# 2230506226.net
KiCad netlist of a schematic drawn in EasyEDA Pro
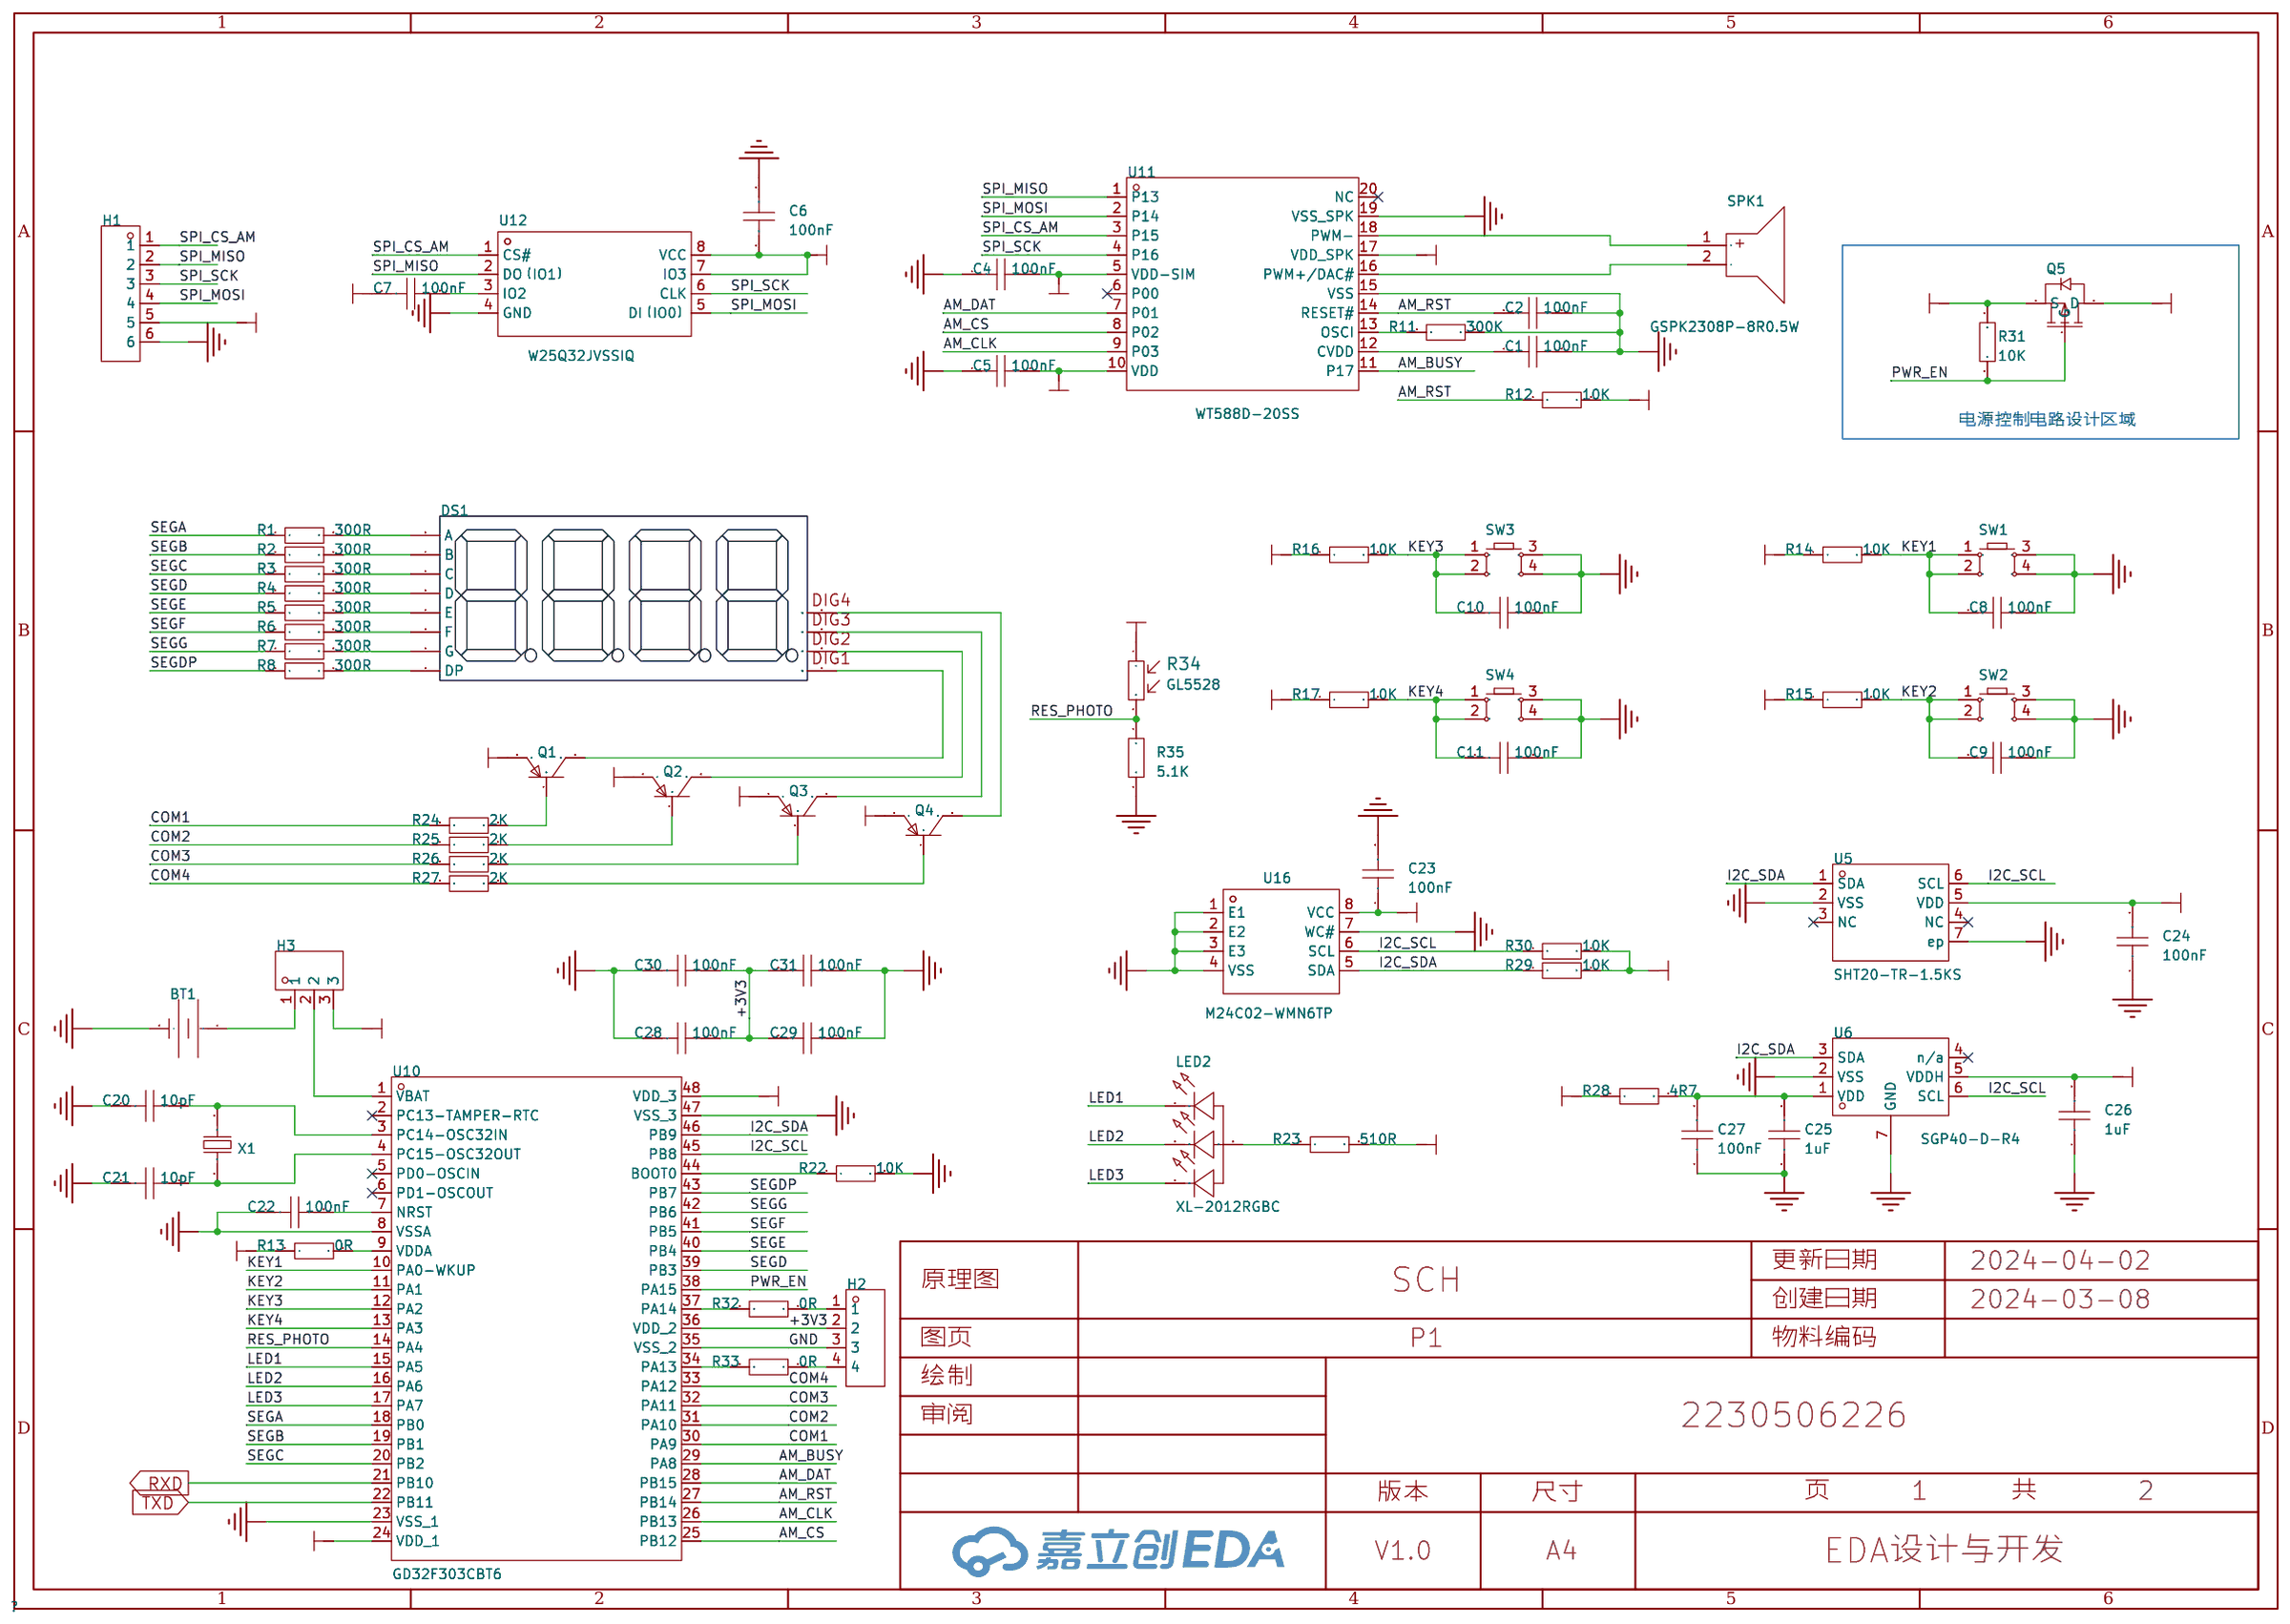
[diagram p0: P1]
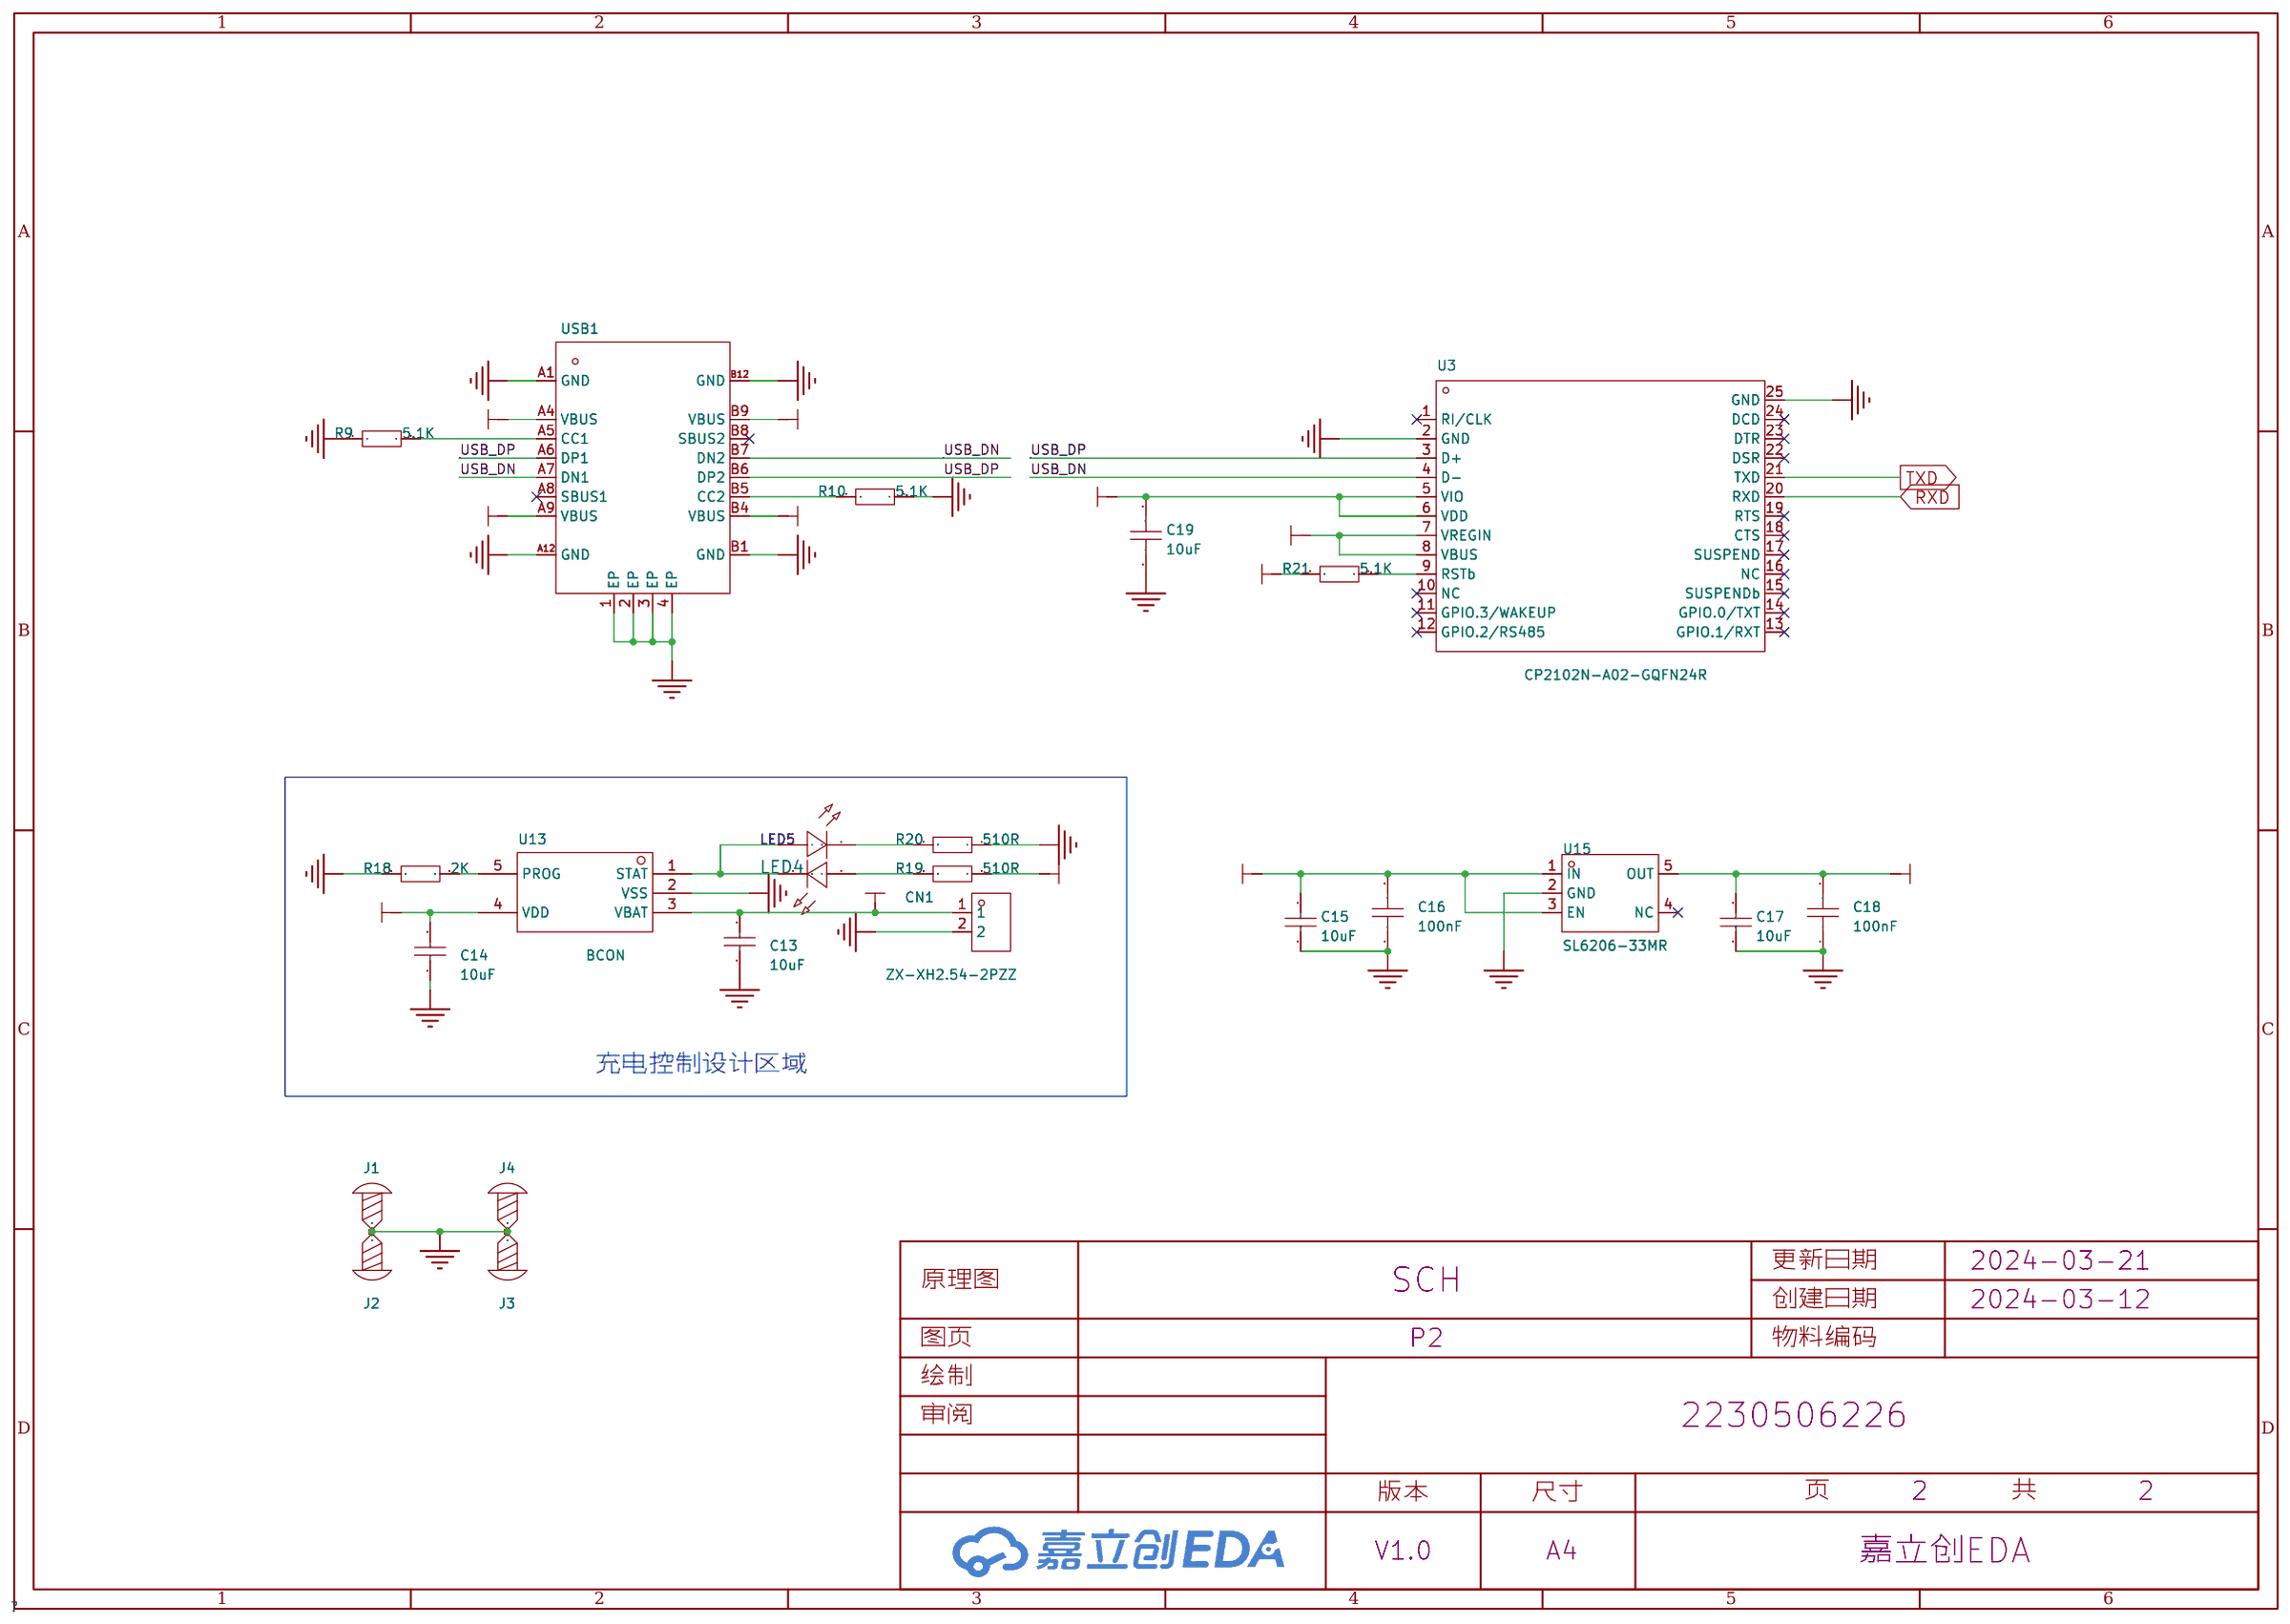
[diagram p1: P2]

(export (version "E")
  (design (tool "Eeschema 10.0.6"))
  (components
    (comp (ref "BT1")
      (value "BS-12-B3AA003")
      (footprint "easyedapro:BAT-SMD_BS-12-B3AA011")
      (description "连接器类型:电池底座;适用电池规格:CR1220;工作温度范围:-25°C~+85°C;")
      (fields (field (name "Manufacturer") "MYOUNG(美阳)"))
      (libsource (lib "easyedapro") (part "BS-12-B3AA003"))
    )
    (comp (ref "C1")
      (value "100nF")
      (footprint "easyedapro:C0805")
      (libsource (lib "easyedapro") (part "CapAcitance"))
    )
    (comp (ref "C2")
      (value "100nF")
      (footprint "easyedapro:C0805")
      (libsource (lib "easyedapro") (part "CapAcitance"))
    )
    (comp (ref "C4")
      (value "100nF")
      (footprint "easyedapro:C0805")
      (libsource (lib "easyedapro") (part "CapAcitance"))
    )
    (comp (ref "C5")
      (value "100nF")
      (footprint "easyedapro:C0805")
      (libsource (lib "easyedapro") (part "CapAcitance"))
    )
    (comp (ref "C6")
      (value "100nF")
      (footprint "easyedapro:C0805")
      (libsource (lib "easyedapro") (part "CapAcitance"))
    )
    (comp (ref "C7")
      (value "100nF")
      (footprint "easyedapro:C0805")
      (libsource (lib "easyedapro") (part "CapAcitance"))
    )
    (comp (ref "C8")
      (value "100nF")
      (footprint "easyedapro:C0805")
      (libsource (lib "easyedapro") (part "CapAcitance"))
    )
    (comp (ref "C9")
      (value "100nF")
      (footprint "easyedapro:C0805")
      (libsource (lib "easyedapro") (part "CapAcitance"))
    )
    (comp (ref "C10")
      (value "100nF")
      (footprint "easyedapro:C0805")
      (libsource (lib "easyedapro") (part "CapAcitance"))
    )
    (comp (ref "C11")
      (value "100nF")
      (footprint "easyedapro:C0805")
      (libsource (lib "easyedapro") (part "CapAcitance"))
    )
    (comp (ref "C20")
      (value "10pF")
      (footprint "easyedapro:C0805")
      (libsource (lib "easyedapro") (part "CapAcitance"))
    )
    (comp (ref "C21")
      (value "10pF")
      (footprint "easyedapro:C0805")
      (libsource (lib "easyedapro") (part "CapAcitance"))
    )
    (comp (ref "C22")
      (value "100nF")
      (footprint "easyedapro:C0805")
      (libsource (lib "easyedapro") (part "CapAcitance"))
    )
    (comp (ref "C23")
      (value "100nF")
      (footprint "easyedapro:C0805")
      (libsource (lib "easyedapro") (part "CapAcitance"))
    )
    (comp (ref "C24")
      (value "100nF")
      (footprint "easyedapro:C0805")
      (libsource (lib "easyedapro") (part "CapAcitance"))
    )
    (comp (ref "C25")
      (value "1uF")
      (footprint "easyedapro:C0805")
      (libsource (lib "easyedapro") (part "CapAcitance"))
    )
    (comp (ref "C26")
      (value "1uF")
      (footprint "easyedapro:C0805")
      (libsource (lib "easyedapro") (part "CapAcitance"))
    )
    (comp (ref "C27")
      (value "100nF")
      (footprint "easyedapro:C0805")
      (libsource (lib "easyedapro") (part "CapAcitance"))
    )
    (comp (ref "C28")
      (value "100nF")
      (footprint "easyedapro:C0805")
      (libsource (lib "easyedapro") (part "CapAcitance"))
    )
    (comp (ref "C29")
      (value "100nF")
      (footprint "easyedapro:C0805")
      (libsource (lib "easyedapro") (part "CapAcitance"))
    )
    (comp (ref "C30")
      (value "100nF")
      (footprint "easyedapro:C0805")
      (libsource (lib "easyedapro") (part "CapAcitance"))
    )
    (comp (ref "C31")
      (value "100nF")
      (footprint "easyedapro:C0805")
      (libsource (lib "easyedapro") (part "CapAcitance"))
    )
    (comp (ref "DS1")
      (value "~")
      (footprint "easyedapro:LED-SEG-TH_FJ5461AH")
      (libsource (lib "easyedapro") (part "LED_SEG_TH_0.56x4"))
    )
    (comp (ref "H1")
      (value "~")
      (footprint "easyedapro:HDR-TH_6P-P2.54-V-F")
      (libsource (lib "easyedapro") (part "Header-Female-2.54_1x6"))
    )
    (comp (ref "H2")
      (value "~")
      (footprint "easyedapro:HDR-TH_4P-P2.54-V-F")
      (libsource (lib "easyedapro") (part "2.54-1*4P母"))
    )
    (comp (ref "H3")
      (value "Jumper3")
      (footprint "easyedapro:HDR-TH_3P-P2.54-V-M-A")
      (libsource (lib "easyedapro") (part "JUMPER3"))
    )
    (comp (ref "LED2")
      (value "XL-2012RGBC")
      (footprint "easyedapro:LED-SMD_4P-L2.0-W1.3-BR")
      (fields (field (name "Manufacturer") "XINGLIGHT(成兴光)"))
      (libsource (lib "easyedapro") (part "XL-2012RGBC"))
    )
    (comp (ref "Q1")
      (value "~")
      (footprint "easyedapro:S8550P_SOT")
      (libsource (lib "easyedapro") (part "PNP"))
    )
    (comp (ref "Q2")
      (value "~")
      (footprint "easyedapro:S8550P_SOT")
      (libsource (lib "easyedapro") (part "PNP"))
    )
    (comp (ref "Q3")
      (value "~")
      (footprint "easyedapro:S8550P_SOT")
      (libsource (lib "easyedapro") (part "PNP"))
    )
    (comp (ref "Q4")
      (value "~")
      (footprint "easyedapro:S8550P_SOT")
      (libsource (lib "easyedapro") (part "PNP"))
    )
    (comp (ref "Q5")
      (value "~")
      (footprint "easyedapro:AO3401A_SOT-23-3")
      (libsource (lib "easyedapro") (part "P_MOS"))
    )
    (comp (ref "R1") (value "300R") (footprint "easyedapro:R0805") (libsource (lib "easyedapro") (part "电阻")))
    (comp (ref "R2") (value "300R") (footprint "easyedapro:R0805") (libsource (lib "easyedapro") (part "电阻")))
    (comp (ref "R3") (value "300R") (footprint "easyedapro:R0805") (libsource (lib "easyedapro") (part "电阻")))
    (comp (ref "R4") (value "300R") (footprint "easyedapro:R0805") (libsource (lib "easyedapro") (part "电阻")))
    (comp (ref "R5") (value "300R") (footprint "easyedapro:R0805") (libsource (lib "easyedapro") (part "电阻")))
    (comp (ref "R6") (value "300R") (footprint "easyedapro:R0805") (libsource (lib "easyedapro") (part "电阻")))
    (comp (ref "R7") (value "300R") (footprint "easyedapro:R0805") (libsource (lib "easyedapro") (part "电阻")))
    (comp (ref "R8") (value "300R") (footprint "easyedapro:R0805") (libsource (lib "easyedapro") (part "电阻")))
    (comp (ref "R11")
      (value "300K")
      (footprint "easyedapro:R0805")
      (libsource (lib "easyedapro") (part "电阻"))
    )
    (comp (ref "R12") (value "10K") (footprint "easyedapro:R0805") (libsource (lib "easyedapro") (part "电阻")))
    (comp (ref "R13") (value "0R") (footprint "easyedapro:R0805") (libsource (lib "easyedapro") (part "电阻")))
    (comp (ref "R14") (value "10K") (footprint "easyedapro:R0805") (libsource (lib "easyedapro") (part "电阻")))
    (comp (ref "R15") (value "10K") (footprint "easyedapro:R0805") (libsource (lib "easyedapro") (part "电阻")))
    (comp (ref "R16") (value "10K") (footprint "easyedapro:R0805") (libsource (lib "easyedapro") (part "电阻")))
    (comp (ref "R17") (value "10K") (footprint "easyedapro:R0805") (libsource (lib "easyedapro") (part "电阻")))
    (comp (ref "R22") (value "10K") (footprint "easyedapro:R0805") (libsource (lib "easyedapro") (part "电阻")))
    (comp (ref "R23")
      (value "510R")
      (footprint "easyedapro:R0805")
      (libsource (lib "easyedapro") (part "电阻"))
    )
    (comp (ref "R24") (value "2K") (footprint "easyedapro:R0805") (libsource (lib "easyedapro") (part "电阻")))
    (comp (ref "R25") (value "2K") (footprint "easyedapro:R0805") (libsource (lib "easyedapro") (part "电阻")))
    (comp (ref "R26") (value "2K") (footprint "easyedapro:R0805") (libsource (lib "easyedapro") (part "电阻")))
    (comp (ref "R27") (value "2K") (footprint "easyedapro:R0805") (libsource (lib "easyedapro") (part "电阻")))
    (comp (ref "R28") (value "4R7") (footprint "easyedapro:R0805") (libsource (lib "easyedapro") (part "电阻")))
    (comp (ref "R29") (value "10K") (footprint "easyedapro:R0805") (libsource (lib "easyedapro") (part "电阻")))
    (comp (ref "R30") (value "10K") (footprint "easyedapro:R0805") (libsource (lib "easyedapro") (part "电阻")))
    (comp (ref "R31") (value "10K") (footprint "easyedapro:R0805") (libsource (lib "easyedapro") (part "电阻")))
    (comp (ref "R32") (value "0R") (footprint "easyedapro:R0805") (libsource (lib "easyedapro") (part "电阻")))
    (comp (ref "R33") (value "0R") (footprint "easyedapro:R0805") (libsource (lib "easyedapro") (part "电阻")))
    (comp (ref "R34")
      (value "GL5528")
      (footprint "easyedapro:RES-TH_L5.1-W4.3-P3.40-D0.5")
      (description "暗电阻:1MΩ;亮电阻 @ 10Lux:8kΩ~20kΩ;光谱峰值(波长):540nm;")
      (fields (field (name "Manufacturer") "森霸"))
      (libsource (lib "easyedapro") (part "GL5528"))
    )
    (comp (ref "R35")
      (value "5.1K")
      (footprint "easyedapro:R0805")
      (libsource (lib "easyedapro") (part "电阻"))
    )
    (comp (ref "SPK1")
      (value "GSPK2308P-8R0.5W")
      (footprint "easyedapro:SPK-TH_BD23.0-P10.00-D0.8-L-RD")
      (fields (field (name "Manufacturer") "INGHAi(赢海)"))
      (libsource (lib "easyedapro") (part "GSPK2308P-8R0.5W"))
    )
    (comp (ref "SW1")
      (value "~")
      (footprint "easyedapro:Key_SMD_12x12x7.3")
      (libsource (lib "easyedapro") (part "轻触按键"))
    )
    (comp (ref "SW2")
      (value "~")
      (footprint "easyedapro:Key_SMD_12x12x7.3")
      (libsource (lib "easyedapro") (part "轻触按键"))
    )
    (comp (ref "SW3")
      (value "~")
      (footprint "easyedapro:Key_SMD_12x12x7.3")
      (libsource (lib "easyedapro") (part "轻触按键"))
    )
    (comp (ref "SW4")
      (value "~")
      (footprint "easyedapro:Key_SMD_12x12x7.3")
      (libsource (lib "easyedapro") (part "轻触按键"))
    )
    (comp (ref "U5")
      (value "SHT20-TR-1.5KS")
      (footprint "easyedapro:DFN-6_L3.0-W3.0-P0.95-TR-EP")
      (description "接口类型:I2C;")
      (fields (field (name "Manufacturer") "Sensirion(瑞士盛思锐)"))
      (libsource (lib "easyedapro") (part "SHT20"))
    )
    (comp (ref "U6")
      (value "SGP40-D-R4")
      (footprint "easyedapro:DFN-6_L2.4-W2.4-P0.80-TL-EP")
      (description "气体类型:空气质量;精度:-;")
      (fields (field (name "Manufacturer") "Sensirion(瑞士盛思锐)"))
      (libsource (lib "easyedapro") (part "SGP40-D-R4"))
    )
    (comp (ref "U10")
      (value "GD32F303CBT6")
      (footprint "easyedapro:LQFP-48_L7.0-W7.0-P0.50-LS9.0-BL")
      (description "CPU内核:CM4;程序存储容量:128KB;RAM总容量:32KB;GPIO端口数量:37;工作电压范围:-;CPU最大主频:120MHz;程序存储器类型:FLASH;")
      (fields (field (name "Manufacturer") "GigaDevice(兆易创新)"))
      (libsource (lib "easyedapro") (part "GD32F303CBT6"))
    )
    (comp (ref "U11")
      (value "WT588D-20SS")
      (footprint "easyedapro:SSOP-20_L7.2-W5.3-P0.65-LS7.8-BL")
      (description "高品质语音芯片")
      (fields (field (name "Manufacturer") "WT(唯创知音)"))
      (libsource (lib "easyedapro") (part "WT588D"))
    )
    (comp (ref "U12")
      (value "W25Q32JVSSIQ")
      (footprint "easyedapro:SOIC-8_L5.3-W5.3-P1.27-LS8.0-BL")
      (description "接口类型:SPI;存储容量:32Mbit;")
      (fields (field (name "Manufacturer") "WINBOND(华邦)"))
      (libsource (lib "easyedapro") (part "W25Q32JVSSIQ"))
    )
    (comp (ref "U16")
      (value "M24C02-WMN6TP")
      (footprint "easyedapro:SOIC-8_L4.9-W3.9-P1.27-LS6.0-BL")
      (description "接口类型:I2C;存储容量:2Kbit;")
      (fields (field (name "Manufacturer") "ST(意法半导体)"))
      (libsource (lib "easyedapro") (part "M24C02-WMN6TP"))
    )
    (comp (ref "X1")
      (value "32.768kHz")
      (footprint "easyedapro:FC-135R_L3.2-W1.5")
      (description "晶振类型:贴片晶振;频率:32.768kHz;常温频差:±20ppm;外接负载电容:12.5pF;")
      (fields (field (name "Manufacturer Part") "Q13FC13500004") (field (name "Manufacturer") "EPSON(爱普生)"))
      (libsource (lib "easyedapro") (part "Q13FC1350000400"))
    )
    (comp (ref "C13")
      (value "10uF")
      (footprint "easyedapro:C1206")
      (description "容值:10uF;精度:±10%;额定电压:50V;材质(温度系数):X5R;")
      (fields
        (field (name "Manufacturer Part") "CL31A106KBHNNNE")
        (field (name "Manufacturer") "SAMSUNG(三星)")
      )
      (libsource (lib "easyedapro") (part "CL31A106KBHNNNE"))
    )
    (comp (ref "C14")
      (value "10uF")
      (footprint "easyedapro:C1206")
      (description "容值:10uF;精度:±10%;额定电压:50V;材质(温度系数):X5R;")
      (fields
        (field (name "Manufacturer Part") "CL31A106KBHNNNE")
        (field (name "Manufacturer") "SAMSUNG(三星)")
      )
      (libsource (lib "easyedapro") (part "CL31A106KBHNNNE"))
    )
    (comp (ref "C15")
      (value "10uF")
      (footprint "easyedapro:C1206")
      (description "容值:10uF;精度:±10%;额定电压:50V;材质(温度系数):X5R;")
      (fields
        (field (name "Manufacturer Part") "CL31A106KBHNNNE")
        (field (name "Manufacturer") "SAMSUNG(三星)")
      )
      (libsource (lib "easyedapro") (part "CL31A106KBHNNNE"))
    )
    (comp (ref "C16")
      (value "100nF")
      (footprint "easyedapro:C0805")
      (libsource (lib "easyedapro") (part "CapAcitance"))
    )
    (comp (ref "C17")
      (value "10uF")
      (footprint "easyedapro:C1206")
      (description "容值:10uF;精度:±10%;额定电压:50V;材质(温度系数):X5R;")
      (fields
        (field (name "Manufacturer Part") "CL31A106KBHNNNE")
        (field (name "Manufacturer") "SAMSUNG(三星)")
      )
      (libsource (lib "easyedapro") (part "CL31A106KBHNNNE"))
    )
    (comp (ref "C18")
      (value "100nF")
      (footprint "easyedapro:C0805")
      (libsource (lib "easyedapro") (part "CapAcitance"))
    )
    (comp (ref "C19")
      (value "10uF")
      (footprint "easyedapro:C0805")
      (libsource (lib "easyedapro") (part "CapAcitance"))
    )
    (comp (ref "CN1")
      (value "ZX-XH2.54-2PZZ")
      (footprint "easyedapro:CONN-TH_2P-P2.50_HX25003-2A")
      (fields (field (name "Manufacturer") "Megastar(兆星)"))
      (libsource (lib "easyedapro") (part "ZX-XH2.54-2PZZ"))
    )
    (comp (ref "J1") (value "~") (footprint "easyedapro:M2螺丝") (libsource (lib "easyedapro") (part "螺丝孔")))
    (comp (ref "J2") (value "~") (footprint "easyedapro:M2螺丝") (libsource (lib "easyedapro") (part "螺丝孔")))
    (comp (ref "J3") (value "~") (footprint "easyedapro:M2螺丝") (libsource (lib "easyedapro") (part "螺丝孔")))
    (comp (ref "J4") (value "~") (footprint "easyedapro:M2螺丝") (libsource (lib "easyedapro") (part "螺丝孔")))
    (comp (ref "LED4")
      (value "~")
      (footprint "easyedapro:LED_0805")
      (libsource (lib "easyedapro") (part "LED_R"))
    )
    (comp (ref "LED5")
      (value "~")
      (footprint "easyedapro:LED_0805")
      (libsource (lib "easyedapro") (part "LED_G"))
    )
    (comp (ref "R9") (value "5.1K") (footprint "easyedapro:R0805") (libsource (lib "easyedapro") (part "电阻")))
    (comp (ref "R10")
      (value "5.1K")
      (footprint "easyedapro:R0805")
      (libsource (lib "easyedapro") (part "电阻"))
    )
    (comp (ref "R18") (value "2K") (footprint "easyedapro:R0805") (libsource (lib "easyedapro") (part "电阻")))
    (comp (ref "R19")
      (value "510R")
      (footprint "easyedapro:R0805")
      (libsource (lib "easyedapro") (part "电阻"))
    )
    (comp (ref "R20")
      (value "510R")
      (footprint "easyedapro:R0805")
      (libsource (lib "easyedapro") (part "电阻"))
    )
    (comp (ref "R21")
      (value "5.1K")
      (footprint "easyedapro:R0805")
      (libsource (lib "easyedapro") (part "电阻"))
    )
    (comp (ref "U3")
      (value "CP2102N-A02-GQFN24R")
      (footprint "easyedapro:QFN-24_L4.0-W4.0-P0.50-TL-EP2.6")
      (description "应用功能:USB转UART;接口协议:UART;")
      (fields (field (name "Manufacturer") "SKYWORKS/SILICON LABS(芯科)"))
      (libsource (lib "easyedapro") (part "CP2102N-A02-GQFN24R"))
    )
    (comp (ref "U13") (value "BCON") (libsource (lib "easyedapro") (part "BCON")))
    (comp (ref "U15")
      (value "SL6206-33MR")
      (footprint "easyedapro:SOT-23-5_L2.9-W1.6-P0.95-LS2.8-BL")
      (description "输出类型:-;")
      (fields (field (name "Manufacturer") "Slkor(萨科微)"))
      (libsource (lib "easyedapro") (part "SL6206-33MR"))
    )
    (comp (ref "USB1")
      (value "~")
      (footprint "easyedapro:USB_TYPE-C-16P")
      (libsource (lib "easyedapro") (part "USB_TYPE-C-16P"))
    )
  )
  (nets
    (net (code "1") (name "+3V3") (class "Default")
      (node (ref "C17") (pin "2") (pinfunction "2_2") (pintype "input"))
      (node (ref "C18") (pin "2") (pinfunction "2_2") (pintype "input"))
      (node (ref "C19") (pin "2") (pinfunction "2_2") (pintype "input"))
      (node (ref "C23") (pin "1") (pinfunction "1_1") (pintype "input"))
      (node (ref "C28") (pin "1") (pinfunction "1_1") (pintype "input"))
      (node (ref "C29") (pin "2") (pinfunction "2_2") (pintype "input"))
      (node (ref "C30") (pin "1") (pinfunction "1_1") (pintype "input"))
      (node (ref "C31") (pin "2") (pinfunction "2_2") (pintype "input"))
      (node (ref "C4") (pin "2") (pinfunction "2_2") (pintype "input"))
      (node (ref "C5") (pin "2") (pinfunction "2_2") (pintype "input"))
      (node (ref "C6") (pin "2") (pinfunction "2_2") (pintype "input"))
      (node (ref "C7") (pin "1") (pinfunction "1_1") (pintype "input"))
      (node (ref "H1") (pin "5") (pinfunction "5_5") (pintype "unspecified"))
      (node (ref "H2") (pin "2") (pinfunction "2_2") (pintype "unspecified"))
      (node (ref "H3") (pin "3") (pinfunction "3_3") (pintype "input"))
      (node (ref "Q1") (pin "2") (pinfunction "E_2") (pintype "input"))
      (node (ref "Q2") (pin "2") (pinfunction "E_2") (pintype "input"))
      (node (ref "Q3") (pin "2") (pinfunction "E_2") (pintype "input"))
      (node (ref "Q4") (pin "2") (pinfunction "E_2") (pintype "input"))
      (node (ref "Q5") (pin "2") (pinfunction "S_2") (pintype "input"))
      (node (ref "R12") (pin "2") (pinfunction "2_2") (pintype "input"))
      (node (ref "R13") (pin "1") (pinfunction "1_1") (pintype "input"))
      (node (ref "R14") (pin "1") (pinfunction "1_1") (pintype "input"))
      (node (ref "R15") (pin "1") (pinfunction "1_1") (pintype "input"))
      (node (ref "R16") (pin "1") (pinfunction "1_1") (pintype "input"))
      (node (ref "R17") (pin "1") (pinfunction "1_1") (pintype "input"))
      (node (ref "R21") (pin "2") (pinfunction "2_2") (pintype "input"))
      (node (ref "R23") (pin "2") (pinfunction "2_2") (pintype "input"))
      (node (ref "R29") (pin "2") (pinfunction "2_2") (pintype "input"))
      (node (ref "R30") (pin "2") (pinfunction "2_2") (pintype "input"))
      (node (ref "R31") (pin "1") (pinfunction "1_1") (pintype "input"))
      (node (ref "R34") (pin "1") (pinfunction "1_1") (pintype "input"))
      (node (ref "U10") (pin "24") (pinfunction "VDD_1_24") (pintype "unspecified"))
      (node (ref "U10") (pin "36") (pinfunction "VDD_2_36") (pintype "unspecified"))
      (node (ref "U10") (pin "48") (pinfunction "VDD_3_48") (pintype "unspecified"))
      (node (ref "U11") (pin "10") (pinfunction "VDD_10") (pintype "input"))
      (node (ref "U11") (pin "17") (pinfunction "VDD_SPK_17") (pintype "input"))
      (node (ref "U11") (pin "5") (pinfunction "VDD-SIM_5") (pintype "input"))
      (node (ref "U12") (pin "7") (pinfunction "IO3_7") (pintype "unspecified"))
      (node (ref "U12") (pin "8") (pinfunction "VCC_8") (pintype "unspecified"))
      (node (ref "U15") (pin "5") (pinfunction "OUT_5") (pintype "unspecified"))
      (node (ref "U16") (pin "8") (pinfunction "VCC_8") (pintype "unspecified"))
      (node (ref "U3") (pin "5") (pinfunction "VIO_5") (pintype "unspecified"))
      (node (ref "U3") (pin "6") (pinfunction "VDD_6") (pintype "unspecified"))
    )
    (net (code "2") (name "+VS") (class "Default")
      (node (ref "C24") (pin "2") (pinfunction "2_2") (pintype "input"))
      (node (ref "C26") (pin "2") (pinfunction "2_2") (pintype "input"))
      (node (ref "Q5") (pin "3") (pinfunction "D_3") (pintype "input"))
      (node (ref "R28") (pin "1") (pinfunction "1_1") (pintype "input"))
      (node (ref "U5") (pin "5") (pinfunction "VDD_5") (pintype "unspecified"))
      (node (ref "U6") (pin "5") (pinfunction "VDDH_5") (pintype "unspecified"))
    )
    (net (code "3") (name "AM_BUSY") (class "Default")
      (node (ref "U10") (pin "29") (pinfunction "PA8_29") (pintype "unspecified"))
      (node (ref "U11") (pin "11") (pinfunction "P17_11") (pintype "input"))
    )
    (net (code "4") (name "AM_CLK") (class "Default")
      (node (ref "U10") (pin "26") (pinfunction "PB13_26") (pintype "unspecified"))
      (node (ref "U11") (pin "9") (pinfunction "P03_9") (pintype "input"))
    )
    (net (code "5") (name "AM_CS") (class "Default")
      (node (ref "U10") (pin "25") (pinfunction "PB12_25") (pintype "unspecified"))
      (node (ref "U11") (pin "8") (pinfunction "P02_8") (pintype "input"))
    )
    (net (code "6") (name "AM_DAT") (class "Default")
      (node (ref "U10") (pin "28") (pinfunction "PB15_28") (pintype "unspecified"))
      (node (ref "U11") (pin "7") (pinfunction "P01_7") (pintype "input"))
    )
    (net (code "7") (name "AM_RST") (class "Default")
      (node (ref "C2") (pin "1") (pinfunction "1_1") (pintype "input"))
      (node (ref "R12") (pin "1") (pinfunction "1_1") (pintype "input"))
      (node (ref "U10") (pin "27") (pinfunction "PB14_27") (pintype "unspecified"))
      (node (ref "U11") (pin "14") (pinfunction "RESET#_14") (pintype "input"))
    )
    (net (code "8") (name "COM1") (class "Default")
      (node (ref "R24") (pin "1") (pinfunction "1_1") (pintype "input"))
      (node (ref "U10") (pin "30") (pinfunction "PA9_30") (pintype "unspecified"))
    )
    (net (code "9") (name "COM2") (class "Default")
      (node (ref "R25") (pin "1") (pinfunction "1_1") (pintype "input"))
      (node (ref "U10") (pin "31") (pinfunction "PA10_31") (pintype "unspecified"))
    )
    (net (code "10") (name "COM3") (class "Default")
      (node (ref "R26") (pin "1") (pinfunction "1_1") (pintype "input"))
      (node (ref "U10") (pin "32") (pinfunction "PA11_32") (pintype "unspecified"))
    )
    (net (code "11") (name "COM4") (class "Default")
      (node (ref "R27") (pin "1") (pinfunction "1_1") (pintype "input"))
      (node (ref "U10") (pin "33") (pinfunction "PA12_33") (pintype "unspecified"))
    )
    (net (code "12") (name "GND") (class "Default")
      (node (ref "BT1") (pin "2") (pinfunction "-_2") (pintype "unspecified"))
      (node (ref "C1") (pin "2") (pinfunction "2_2") (pintype "input"))
      (node (ref "C10") (pin "2") (pinfunction "2_2") (pintype "input"))
      (node (ref "C11") (pin "2") (pinfunction "2_2") (pintype "input"))
      (node (ref "C13") (pin "2") (pinfunction "2_2") (pintype "input"))
      (node (ref "C14") (pin "2") (pinfunction "2_2") (pintype "input"))
      (node (ref "C15") (pin "1") (pinfunction "1_1") (pintype "input"))
      (node (ref "C16") (pin "1") (pinfunction "1_1") (pintype "input"))
      (node (ref "C17") (pin "1") (pinfunction "1_1") (pintype "input"))
      (node (ref "C18") (pin "1") (pinfunction "1_1") (pintype "input"))
      (node (ref "C19") (pin "1") (pinfunction "1_1") (pintype "input"))
      (node (ref "C2") (pin "2") (pinfunction "2_2") (pintype "input"))
      (node (ref "C20") (pin "1") (pinfunction "1_1") (pintype "input"))
      (node (ref "C21") (pin "1") (pinfunction "1_1") (pintype "input"))
      (node (ref "C22") (pin "1") (pinfunction "1_1") (pintype "input"))
      (node (ref "C23") (pin "2") (pinfunction "2_2") (pintype "input"))
      (node (ref "C24") (pin "1") (pinfunction "1_1") (pintype "input"))
      (node (ref "C25") (pin "1") (pinfunction "1_1") (pintype "input"))
      (node (ref "C26") (pin "1") (pinfunction "1_1") (pintype "input"))
      (node (ref "C27") (pin "1") (pinfunction "1_1") (pintype "input"))
      (node (ref "C28") (pin "2") (pinfunction "2_2") (pintype "input"))
      (node (ref "C29") (pin "1") (pinfunction "1_1") (pintype "input"))
      (node (ref "C30") (pin "2") (pinfunction "2_2") (pintype "input"))
      (node (ref "C31") (pin "1") (pinfunction "1_1") (pintype "input"))
      (node (ref "C4") (pin "1") (pinfunction "1_1") (pintype "input"))
      (node (ref "C5") (pin "1") (pinfunction "1_1") (pintype "input"))
      (node (ref "C6") (pin "1") (pinfunction "1_1") (pintype "input"))
      (node (ref "C8") (pin "2") (pinfunction "2_2") (pintype "input"))
      (node (ref "C9") (pin "2") (pinfunction "2_2") (pintype "input"))
      (node (ref "CN1") (pin "2") (pinfunction "2_2") (pintype "unspecified"))
      (node (ref "H1") (pin "6") (pinfunction "6_6") (pintype "unspecified"))
      (node (ref "H2") (pin "3") (pinfunction "3_3") (pintype "unspecified"))
      (node (ref "J1") (pin "1") (pinfunction "1_1") (pintype "input"))
      (node (ref "J2") (pin "1") (pinfunction "1_1") (pintype "input"))
      (node (ref "J3") (pin "1") (pinfunction "1_1") (pintype "input"))
      (node (ref "J4") (pin "1") (pinfunction "1_1") (pintype "input"))
      (node (ref "R10") (pin "1") (pinfunction "1_1") (pintype "input"))
      (node (ref "R11") (pin "2") (pinfunction "2_2") (pintype "input"))
      (node (ref "R18") (pin "2") (pinfunction "2_2") (pintype "input"))
      (node (ref "R20") (pin "1") (pinfunction "1_1") (pintype "input"))
      (node (ref "R22") (pin "2") (pinfunction "2_2") (pintype "input"))
      (node (ref "R35") (pin "2") (pinfunction "2_2") (pintype "input"))
      (node (ref "R9") (pin "1") (pinfunction "1_1") (pintype "input"))
      (node (ref "SW1") (pin "3") (pinfunction "3_3") (pintype "input"))
      (node (ref "SW1") (pin "4") (pinfunction "4_4") (pintype "input"))
      (node (ref "SW2") (pin "3") (pinfunction "3_3") (pintype "input"))
      (node (ref "SW2") (pin "4") (pinfunction "4_4") (pintype "input"))
      (node (ref "SW3") (pin "3") (pinfunction "3_3") (pintype "input"))
      (node (ref "SW3") (pin "4") (pinfunction "4_4") (pintype "input"))
      (node (ref "SW4") (pin "3") (pinfunction "3_3") (pintype "input"))
      (node (ref "SW4") (pin "4") (pinfunction "4_4") (pintype "input"))
      (node (ref "U10") (pin "23") (pinfunction "VSS_1_23") (pintype "unspecified"))
      (node (ref "U10") (pin "35") (pinfunction "VSS_2_35") (pintype "unspecified"))
      (node (ref "U10") (pin "47") (pinfunction "VSS_3_47") (pintype "unspecified"))
      (node (ref "U10") (pin "8") (pinfunction "VSSA_8") (pintype "unspecified"))
      (node (ref "U11") (pin "15") (pinfunction "VSS_15") (pintype "input"))
      (node (ref "U11") (pin "19") (pinfunction "VSS_SPK_19") (pintype "input"))
      (node (ref "U12") (pin "4") (pinfunction "GND_4") (pintype "unspecified"))
      (node (ref "U13") (pin "2") (pinfunction "VSS_2") (pintype "input"))
      (node (ref "U15") (pin "2") (pinfunction "GND_2") (pintype "unspecified"))
      (node (ref "U16") (pin "1") (pinfunction "E1_1") (pintype "unspecified"))
      (node (ref "U16") (pin "2") (pinfunction "E2_2") (pintype "unspecified"))
      (node (ref "U16") (pin "3") (pinfunction "E3_3") (pintype "unspecified"))
      (node (ref "U16") (pin "4") (pinfunction "VSS_4") (pintype "unspecified"))
      (node (ref "U16") (pin "7") (pinfunction "WC#_7") (pintype "unspecified"))
      (node (ref "U3") (pin "2") (pinfunction "GND_2") (pintype "unspecified"))
      (node (ref "U3") (pin "25") (pinfunction "GND_25") (pintype "unspecified"))
      (node (ref "U5") (pin "2") (pinfunction "VSS_2") (pintype "unspecified"))
      (node (ref "U5") (pin "7") (pinfunction "ep_7") (pintype "unspecified"))
      (node (ref "U6") (pin "2") (pinfunction "VSS_2") (pintype "unspecified"))
      (node (ref "U6") (pin "7") (pinfunction "GND_7") (pintype "unspecified"))
      (node (ref "USB1") (pin "1") (pinfunction "EP_1") (pintype "input"))
      (node (ref "USB1") (pin "2") (pinfunction "EP_2") (pintype "input"))
      (node (ref "USB1") (pin "3") (pinfunction "EP_3") (pintype "input"))
      (node (ref "USB1") (pin "4") (pinfunction "EP_4") (pintype "input"))
      (node (ref "USB1") (pin "A1") (pinfunction "GND_A1") (pintype "input"))
      (node (ref "USB1") (pin "A12") (pinfunction "GND_A12") (pintype "input"))
      (node (ref "USB1") (pin "B1") (pinfunction "GND_B1") (pintype "input"))
      (node (ref "USB1") (pin "B12") (pinfunction "GND_B12") (pintype "input"))
    )
    (net (code "13") (name "I2C_SCL") (class "Default")
      (node (ref "R30") (pin "1") (pinfunction "1_1") (pintype "input"))
      (node (ref "U10") (pin "45") (pinfunction "PB8_45") (pintype "unspecified"))
      (node (ref "U16") (pin "6") (pinfunction "SCL_6") (pintype "unspecified"))
      (node (ref "U5") (pin "6") (pinfunction "SCL_6") (pintype "unspecified"))
      (node (ref "U6") (pin "6") (pinfunction "SCL_6") (pintype "unspecified"))
    )
    (net (code "14") (name "I2C_SDA") (class "Default")
      (node (ref "R29") (pin "1") (pinfunction "1_1") (pintype "input"))
      (node (ref "U10") (pin "46") (pinfunction "PB9_46") (pintype "unspecified"))
      (node (ref "U16") (pin "5") (pinfunction "SDA_5") (pintype "unspecified"))
      (node (ref "U5") (pin "1") (pinfunction "SDA_1") (pintype "unspecified"))
      (node (ref "U6") (pin "3") (pinfunction "SDA_3") (pintype "unspecified"))
    )
    (net (code "15") (name "KEY1") (class "Default")
      (node (ref "C8") (pin "1") (pinfunction "1_1") (pintype "input"))
      (node (ref "R14") (pin "2") (pinfunction "2_2") (pintype "input"))
      (node (ref "SW1") (pin "1") (pinfunction "1_1") (pintype "input"))
      (node (ref "SW1") (pin "2") (pinfunction "2_2") (pintype "input"))
      (node (ref "U10") (pin "10") (pinfunction "PA0-WKUP_10") (pintype "unspecified"))
    )
    (net (code "16") (name "KEY2") (class "Default")
      (node (ref "C9") (pin "1") (pinfunction "1_1") (pintype "input"))
      (node (ref "R15") (pin "2") (pinfunction "2_2") (pintype "input"))
      (node (ref "SW2") (pin "1") (pinfunction "1_1") (pintype "input"))
      (node (ref "SW2") (pin "2") (pinfunction "2_2") (pintype "input"))
      (node (ref "U10") (pin "11") (pinfunction "PA1_11") (pintype "unspecified"))
    )
    (net (code "17") (name "KEY3") (class "Default")
      (node (ref "C10") (pin "1") (pinfunction "1_1") (pintype "input"))
      (node (ref "R16") (pin "2") (pinfunction "2_2") (pintype "input"))
      (node (ref "SW3") (pin "1") (pinfunction "1_1") (pintype "input"))
      (node (ref "SW3") (pin "2") (pinfunction "2_2") (pintype "input"))
      (node (ref "U10") (pin "12") (pinfunction "PA2_12") (pintype "unspecified"))
    )
    (net (code "18") (name "KEY4") (class "Default")
      (node (ref "C11") (pin "1") (pinfunction "1_1") (pintype "input"))
      (node (ref "R17") (pin "2") (pinfunction "2_2") (pintype "input"))
      (node (ref "SW4") (pin "1") (pinfunction "1_1") (pintype "input"))
      (node (ref "SW4") (pin "2") (pinfunction "2_2") (pintype "input"))
      (node (ref "U10") (pin "13") (pinfunction "PA3_13") (pintype "unspecified"))
    )
    (net (code "19") (name "LED1") (class "Default")
      (node (ref "LED2") (pin "1") (pinfunction "1_1") (pintype "unspecified"))
      (node (ref "U10") (pin "15") (pinfunction "PA5_15") (pintype "unspecified"))
    )
    (net (code "20") (name "LED2") (class "Default")
      (node (ref "LED2") (pin "2") (pinfunction "2_2") (pintype "unspecified"))
      (node (ref "U10") (pin "16") (pinfunction "PA6_16") (pintype "unspecified"))
    )
    (net (code "21") (name "LED3") (class "Default")
      (node (ref "LED2") (pin "4") (pinfunction "4_4") (pintype "unspecified"))
      (node (ref "U10") (pin "17") (pinfunction "PA7_17") (pintype "unspecified"))
    )
    (net (code "22") (name "Net-(BT1-+)") (class "Default")
      (node (ref "BT1") (pin "1") (pinfunction "+_1") (pintype "unspecified"))
      (node (ref "H3") (pin "1") (pinfunction "1_1") (pintype "input"))
    )
    (net (code "23") (name "Net-(DS1-A)") (class "Default")
      (node (ref "DS1") (pin "11") (pinfunction "A_11") (pintype "input"))
      (node (ref "R1") (pin "2") (pinfunction "2_2") (pintype "input"))
    )
    (net (code "24") (name "Net-(DS1-B)") (class "Default")
      (node (ref "DS1") (pin "7") (pinfunction "B_7") (pintype "input"))
      (node (ref "R2") (pin "2") (pinfunction "2_2") (pintype "input"))
    )
    (net (code "25") (name "Net-(DS1-C)") (class "Default")
      (node (ref "DS1") (pin "4") (pinfunction "C_4") (pintype "input"))
      (node (ref "R3") (pin "2") (pinfunction "2_2") (pintype "input"))
    )
    (net (code "26") (name "Net-(DS1-D)") (class "Default")
      (node (ref "DS1") (pin "2") (pinfunction "D_2") (pintype "input"))
      (node (ref "R4") (pin "2") (pinfunction "2_2") (pintype "input"))
    )
    (net (code "27") (name "Net-(DS1-DIG1)") (class "Default")
      (node (ref "DS1") (pin "12") (pinfunction "DIG1_12") (pintype "input"))
      (node (ref "Q1") (pin "3") (pinfunction "C_3") (pintype "input"))
    )
    (net (code "28") (name "Net-(DS1-DIG2)") (class "Default")
      (node (ref "DS1") (pin "9") (pinfunction "DIG2_9") (pintype "input"))
      (node (ref "Q2") (pin "3") (pinfunction "C_3") (pintype "input"))
    )
    (net (code "29") (name "Net-(DS1-DIG3)") (class "Default")
      (node (ref "DS1") (pin "8") (pinfunction "DIG3_8") (pintype "input"))
      (node (ref "Q3") (pin "3") (pinfunction "C_3") (pintype "input"))
    )
    (net (code "30") (name "Net-(DS1-DIG4)") (class "Default")
      (node (ref "DS1") (pin "6") (pinfunction "DIG4_6") (pintype "input"))
      (node (ref "Q4") (pin "3") (pinfunction "C_3") (pintype "input"))
    )
    (net (code "31") (name "Net-(DS1-DP)") (class "Default")
      (node (ref "DS1") (pin "3") (pinfunction "DP_3") (pintype "input"))
      (node (ref "R8") (pin "2") (pinfunction "2_2") (pintype "input"))
    )
    (net (code "32") (name "Net-(DS1-E)") (class "Default")
      (node (ref "DS1") (pin "1") (pinfunction "E_1") (pintype "input"))
      (node (ref "R5") (pin "2") (pinfunction "2_2") (pintype "input"))
    )
    (net (code "33") (name "Net-(DS1-F)") (class "Default")
      (node (ref "DS1") (pin "10") (pinfunction "F_10") (pintype "input"))
      (node (ref "R6") (pin "2") (pinfunction "2_2") (pintype "input"))
    )
    (net (code "34") (name "Net-(DS1-G)") (class "Default")
      (node (ref "DS1") (pin "5") (pinfunction "G_5") (pintype "input"))
      (node (ref "R7") (pin "2") (pinfunction "2_2") (pintype "input"))
    )
    (net (code "35") (name "Net-(H2-Pad1)") (class "Default")
      (node (ref "H2") (pin "1") (pinfunction "1_1") (pintype "unspecified"))
      (node (ref "R32") (pin "2") (pinfunction "2_2") (pintype "input"))
    )
    (net (code "36") (name "Net-(H2-Pad4)") (class "Default")
      (node (ref "H2") (pin "4") (pinfunction "4_4") (pintype "unspecified"))
      (node (ref "R33") (pin "2") (pinfunction "2_2") (pintype "input"))
    )
    (net (code "37") (name "Net-(LED2-Pad3)") (class "Default")
      (node (ref "LED2") (pin "3") (pinfunction "3_3") (pintype "unspecified"))
      (node (ref "R23") (pin "1") (pinfunction "1_1") (pintype "input"))
    )
    (net (code "38") (name "Net-(LED4-A)") (class "Default")
      (node (ref "LED4") (pin "2") (pinfunction "A_2") (pintype "input"))
      (node (ref "R19") (pin "2") (pinfunction "2_2") (pintype "input"))
    )
    (net (code "39") (name "Net-(LED4-C)") (class "Default")
      (node (ref "LED4") (pin "1") (pinfunction "C_1") (pintype "input"))
      (node (ref "LED5") (pin "2") (pinfunction "A_2") (pintype "input"))
      (node (ref "U13") (pin "1") (pinfunction "STAT_1") (pintype "input"))
    )
    (net (code "40") (name "Net-(LED5-C)") (class "Default")
      (node (ref "LED5") (pin "1") (pinfunction "C_1") (pintype "input"))
      (node (ref "R20") (pin "2") (pinfunction "2_2") (pintype "input"))
    )
    (net (code "41") (name "Net-(Q1-B)") (class "Default")
      (node (ref "Q1") (pin "1") (pinfunction "B_1") (pintype "input"))
      (node (ref "R24") (pin "2") (pinfunction "2_2") (pintype "input"))
    )
    (net (code "42") (name "Net-(Q2-B)") (class "Default")
      (node (ref "Q2") (pin "1") (pinfunction "B_1") (pintype "input"))
      (node (ref "R25") (pin "2") (pinfunction "2_2") (pintype "input"))
    )
    (net (code "43") (name "Net-(Q3-B)") (class "Default")
      (node (ref "Q3") (pin "1") (pinfunction "B_1") (pintype "input"))
      (node (ref "R26") (pin "2") (pinfunction "2_2") (pintype "input"))
    )
    (net (code "44") (name "Net-(Q4-B)") (class "Default")
      (node (ref "Q4") (pin "1") (pinfunction "B_1") (pintype "input"))
      (node (ref "R27") (pin "2") (pinfunction "2_2") (pintype "input"))
    )
    (net (code "45") (name "Net-(SPK1-+)") (class "Default")
      (node (ref "SPK1") (pin "1") (pinfunction "+_1") (pintype "input"))
      (node (ref "U11") (pin "18") (pinfunction "PWM-_18") (pintype "input"))
    )
    (net (code "46") (name "Net-(SPK1--)") (class "Default")
      (node (ref "SPK1") (pin "2") (pinfunction "-_2") (pintype "input"))
      (node (ref "U11") (pin "16") (pinfunction "PWM+/DAC#_16") (pintype "input"))
    )
    (net (code "47") (name "Net-(U3-RSTb)") (class "Default")
      (node (ref "R21") (pin "1") (pinfunction "1_1") (pintype "input"))
      (node (ref "U3") (pin "9") (pinfunction "RSTb_9") (pintype "unspecified"))
    )
    (net (code "48") (name "Net-(U6-VDD)") (class "Default")
      (node (ref "C25") (pin "2") (pinfunction "2_2") (pintype "input"))
      (node (ref "C27") (pin "2") (pinfunction "2_2") (pintype "input"))
      (node (ref "R28") (pin "2") (pinfunction "2_2") (pintype "input"))
      (node (ref "U6") (pin "1") (pinfunction "VDD_1") (pintype "unspecified"))
    )
    (net (code "49") (name "Net-(U10-BOOT0)") (class "Default")
      (node (ref "R22") (pin "1") (pinfunction "1_1") (pintype "input"))
      (node (ref "U10") (pin "44") (pinfunction "BOOT0_44") (pintype "unspecified"))
    )
    (net (code "50") (name "Net-(U10-NRST)") (class "Default")
      (node (ref "C22") (pin "2") (pinfunction "2_2") (pintype "input"))
      (node (ref "U10") (pin "7") (pinfunction "NRST_7") (pintype "unspecified"))
    )
    (net (code "51") (name "Net-(U10-PA13)") (class "Default")
      (node (ref "R33") (pin "1") (pinfunction "1_1") (pintype "input"))
      (node (ref "U10") (pin "34") (pinfunction "PA13_34") (pintype "unspecified"))
    )
    (net (code "52") (name "Net-(U10-PA14)") (class "Default")
      (node (ref "R32") (pin "1") (pinfunction "1_1") (pintype "input"))
      (node (ref "U10") (pin "37") (pinfunction "PA14_37") (pintype "unspecified"))
    )
    (net (code "53") (name "Net-(U10-PC14-OSC32IN)") (class "Default")
      (node (ref "C20") (pin "2") (pinfunction "2_2") (pintype "input"))
      (node (ref "U10") (pin "3") (pinfunction "PC14-OSC32IN_3") (pintype "unspecified"))
      (node (ref "X1") (pin "1") (pinfunction "1_1") (pintype "unspecified"))
    )
    (net (code "54") (name "Net-(U10-PC15-OSC32OUT)") (class "Default")
      (node (ref "C21") (pin "2") (pinfunction "2_2") (pintype "input"))
      (node (ref "U10") (pin "4") (pinfunction "PC15-OSC32OUT_4") (pintype "unspecified"))
      (node (ref "X1") (pin "2") (pinfunction "2_2") (pintype "unspecified"))
    )
    (net (code "55") (name "Net-(U10-VBAT)") (class "Default")
      (node (ref "H3") (pin "2") (pinfunction "2_2") (pintype "input"))
      (node (ref "U10") (pin "1") (pinfunction "VBAT_1") (pintype "unspecified"))
    )
    (net (code "56") (name "Net-(U10-VDDA)") (class "Default")
      (node (ref "R13") (pin "2") (pinfunction "2_2") (pintype "input"))
      (node (ref "U10") (pin "9") (pinfunction "VDDA_9") (pintype "unspecified"))
    )
    (net (code "57") (name "Net-(U11-CVDD)") (class "Default")
      (node (ref "C1") (pin "1") (pinfunction "1_1") (pintype "input"))
      (node (ref "U11") (pin "12") (pinfunction "CVDD_12") (pintype "input"))
    )
    (net (code "58") (name "Net-(U11-OSCI)") (class "Default")
      (node (ref "R11") (pin "1") (pinfunction "1_1") (pintype "input"))
      (node (ref "U11") (pin "13") (pinfunction "OSCI_13") (pintype "input"))
    )
    (net (code "59") (name "Net-(U12-IO2)") (class "Default")
      (node (ref "C7") (pin "2") (pinfunction "2_2") (pintype "input"))
      (node (ref "U12") (pin "3") (pinfunction "IO2_3") (pintype "unspecified"))
    )
    (net (code "60") (name "Net-(U13-PROG)") (class "Default")
      (node (ref "R18") (pin "1") (pinfunction "1_1") (pintype "input"))
      (node (ref "U13") (pin "5") (pinfunction "PROG_5") (pintype "input"))
    )
    (net (code "61") (name "Net-(USB1-CC1)") (class "Default")
      (node (ref "R9") (pin "2") (pinfunction "2_2") (pintype "input"))
      (node (ref "USB1") (pin "A5") (pinfunction "CC1_A5") (pintype "input"))
    )
    (net (code "62") (name "Net-(USB1-CC2)") (class "Default")
      (node (ref "R10") (pin "2") (pinfunction "2_2") (pintype "input"))
      (node (ref "USB1") (pin "B5") (pinfunction "CC2_B5") (pintype "input"))
    )
    (net (code "63") (name "PWR_EN") (class "Default")
      (node (ref "Q5") (pin "1") (pinfunction "G_1") (pintype "input"))
      (node (ref "R31") (pin "2") (pinfunction "2_2") (pintype "input"))
      (node (ref "U10") (pin "38") (pinfunction "PA15_38") (pintype "unspecified"))
    )
    (net (code "64") (name "RES_PHOTO") (class "Default")
      (node (ref "R34") (pin "2") (pinfunction "2_2") (pintype "input"))
      (node (ref "R35") (pin "1") (pinfunction "1_1") (pintype "input"))
      (node (ref "U10") (pin "14") (pinfunction "PA4_14") (pintype "unspecified"))
    )
    (net (code "65") (name "RXD") (class "Default")
      (node (ref "U10") (pin "21") (pinfunction "PB10_21") (pintype "unspecified"))
      (node (ref "U3") (pin "20") (pinfunction "RXD_20") (pintype "unspecified"))
    )
    (net (code "66") (name "SEGA") (class "Default")
      (node (ref "R1") (pin "1") (pinfunction "1_1") (pintype "input"))
      (node (ref "U10") (pin "18") (pinfunction "PB0_18") (pintype "unspecified"))
    )
    (net (code "67") (name "SEGB") (class "Default")
      (node (ref "R2") (pin "1") (pinfunction "1_1") (pintype "input"))
      (node (ref "U10") (pin "19") (pinfunction "PB1_19") (pintype "unspecified"))
    )
    (net (code "68") (name "SEGC") (class "Default")
      (node (ref "R3") (pin "1") (pinfunction "1_1") (pintype "input"))
      (node (ref "U10") (pin "20") (pinfunction "PB2_20") (pintype "unspecified"))
    )
    (net (code "69") (name "SEGD") (class "Default")
      (node (ref "R4") (pin "1") (pinfunction "1_1") (pintype "input"))
      (node (ref "U10") (pin "39") (pinfunction "PB3_39") (pintype "unspecified"))
    )
    (net (code "70") (name "SEGDP") (class "Default")
      (node (ref "R8") (pin "1") (pinfunction "1_1") (pintype "input"))
      (node (ref "U10") (pin "43") (pinfunction "PB7_43") (pintype "unspecified"))
    )
    (net (code "71") (name "SEGE") (class "Default")
      (node (ref "R5") (pin "1") (pinfunction "1_1") (pintype "input"))
      (node (ref "U10") (pin "40") (pinfunction "PB4_40") (pintype "unspecified"))
    )
    (net (code "72") (name "SEGF") (class "Default")
      (node (ref "R6") (pin "1") (pinfunction "1_1") (pintype "input"))
      (node (ref "U10") (pin "41") (pinfunction "PB5_41") (pintype "unspecified"))
    )
    (net (code "73") (name "SEGG") (class "Default")
      (node (ref "R7") (pin "1") (pinfunction "1_1") (pintype "input"))
      (node (ref "U10") (pin "42") (pinfunction "PB6_42") (pintype "unspecified"))
    )
    (net (code "74") (name "SPI_CS_AM") (class "Default")
      (node (ref "H1") (pin "1") (pinfunction "1_1") (pintype "unspecified"))
      (node (ref "U11") (pin "3") (pinfunction "P15_3") (pintype "input"))
      (node (ref "U12") (pin "1") (pinfunction "CS#_1") (pintype "unspecified"))
    )
    (net (code "75") (name "SPI_MISO") (class "Default")
      (node (ref "H1") (pin "2") (pinfunction "2_2") (pintype "unspecified"))
      (node (ref "U11") (pin "1") (pinfunction "P13_1") (pintype "input"))
      (node (ref "U12") (pin "2") (pinfunction "DO（IO1）_2") (pintype "unspecified"))
    )
    (net (code "76") (name "SPI_MOSI") (class "Default")
      (node (ref "H1") (pin "4") (pinfunction "4_4") (pintype "unspecified"))
      (node (ref "U11") (pin "2") (pinfunction "P14_2") (pintype "input"))
      (node (ref "U12") (pin "5") (pinfunction "DI（IO0）_5") (pintype "unspecified"))
    )
    (net (code "77") (name "SPI_SCK") (class "Default")
      (node (ref "H1") (pin "3") (pinfunction "3_3") (pintype "unspecified"))
      (node (ref "U11") (pin "4") (pinfunction "P16_4") (pintype "input"))
      (node (ref "U12") (pin "6") (pinfunction "CLK_6") (pintype "unspecified"))
    )
    (net (code "78") (name "TXD") (class "Default")
      (node (ref "U10") (pin "22") (pinfunction "PB11_22") (pintype "unspecified"))
      (node (ref "U3") (pin "21") (pinfunction "TXD_21") (pintype "unspecified"))
    )
    (net (code "79") (name "USB_DN") (class "Default")
      (node (ref "U3") (pin "4") (pinfunction "D-_4") (pintype "unspecified"))
      (node (ref "USB1") (pin "A7") (pinfunction "DN1_A7") (pintype "input"))
      (node (ref "USB1") (pin "B7") (pinfunction "DN2_B7") (pintype "input"))
    )
    (net (code "80") (name "USB_DP") (class "Default")
      (node (ref "U3") (pin "3") (pinfunction "D+_3") (pintype "unspecified"))
      (node (ref "USB1") (pin "A6") (pinfunction "DP1_A6") (pintype "input"))
      (node (ref "USB1") (pin "B6") (pinfunction "DP2_B6") (pintype "input"))
    )
    (net (code "81") (name "VBAT") (class "Default")
      (node (ref "C13") (pin "1") (pinfunction "1_1") (pintype "input"))
      (node (ref "C15") (pin "2") (pinfunction "2_2") (pintype "input"))
      (node (ref "C16") (pin "2") (pinfunction "2_2") (pintype "input"))
      (node (ref "CN1") (pin "1") (pinfunction "1_1") (pintype "unspecified"))
      (node (ref "U13") (pin "3") (pinfunction "VBAT_3") (pintype "input"))
      (node (ref "U15") (pin "1") (pinfunction "IN_1") (pintype "unspecified"))
      (node (ref "U15") (pin "3") (pinfunction "EN_3") (pintype "unspecified"))
    )
    (net (code "82") (name "VBUS") (class "Default")
      (node (ref "C14") (pin "1") (pinfunction "1_1") (pintype "input"))
      (node (ref "R19") (pin "1") (pinfunction "1_1") (pintype "input"))
      (node (ref "U13") (pin "4") (pinfunction "VDD_4") (pintype "input"))
      (node (ref "U3") (pin "7") (pinfunction "VREGIN_7") (pintype "unspecified"))
      (node (ref "U3") (pin "8") (pinfunction "VBUS_8") (pintype "unspecified"))
      (node (ref "USB1") (pin "A4") (pinfunction "VBUS_A4") (pintype "input"))
      (node (ref "USB1") (pin "A9") (pinfunction "VBUS_A9") (pintype "input"))
      (node (ref "USB1") (pin "B4") (pinfunction "VBUS_B4") (pintype "input"))
      (node (ref "USB1") (pin "B9") (pinfunction "VBUS_B9") (pintype "input"))
    )
    (net (code "83") (name "unconnected-(U3-CTS-Pad18)") (class "Default")
      (node (ref "U3") (pin "18") (pinfunction "CTS_18") (pintype "unspecified+no_connect"))
    )
    (net (code "84") (name "unconnected-(U3-DCD-Pad24)") (class "Default")
      (node (ref "U3") (pin "24") (pinfunction "DCD_24") (pintype "unspecified+no_connect"))
    )
    (net (code "85") (name "unconnected-(U3-DSR-Pad22)") (class "Default")
      (node (ref "U3") (pin "22") (pinfunction "DSR_22") (pintype "unspecified+no_connect"))
    )
    (net (code "86") (name "unconnected-(U3-DTR-Pad23)") (class "Default")
      (node (ref "U3") (pin "23") (pinfunction "DTR_23") (pintype "unspecified+no_connect"))
    )
    (net (code "87") (name "unconnected-(U3-GPIO.0{slash}TXT-Pad14)") (class "Default")
      (node (ref "U3") (pin "14") (pinfunction "GPIO.0/TXT_14") (pintype "unspecified+no_connect"))
    )
    (net (code "88") (name "unconnected-(U3-GPIO.1{slash}RXT-Pad13)") (class "Default")
      (node (ref "U3") (pin "13") (pinfunction "GPIO.1/RXT_13") (pintype "unspecified+no_connect"))
    )
    (net (code "89") (name "unconnected-(U3-GPIO.2{slash}RS485-Pad12)") (class "Default")
      (node (ref "U3") (pin "12") (pinfunction "GPIO.2/RS485_12") (pintype "unspecified+no_connect"))
    )
    (net (code "90") (name "unconnected-(U3-GPIO.3{slash}WAKEUP-Pad11)") (class "Default")
      (node (ref "U3") (pin "11") (pinfunction "GPIO.3/WAKEUP_11") (pintype "unspecified+no_connect"))
    )
    (net (code "91") (name "unconnected-(U3-NC-Pad10)") (class "Default")
      (node (ref "U3") (pin "10") (pinfunction "NC_10") (pintype "unspecified+no_connect"))
    )
    (net (code "92") (name "unconnected-(U3-NC-Pad16)") (class "Default")
      (node (ref "U3") (pin "16") (pinfunction "NC_16") (pintype "unspecified+no_connect"))
    )
    (net (code "93") (name "unconnected-(U3-RI{slash}CLK-Pad1)") (class "Default")
      (node (ref "U3") (pin "1") (pinfunction "RI/CLK_1") (pintype "unspecified+no_connect"))
    )
    (net (code "94") (name "unconnected-(U3-RTS-Pad19)") (class "Default")
      (node (ref "U3") (pin "19") (pinfunction "RTS_19") (pintype "unspecified+no_connect"))
    )
    (net (code "95") (name "unconnected-(U3-SUSPEND-Pad17)") (class "Default")
      (node (ref "U3") (pin "17") (pinfunction "SUSPEND_17") (pintype "unspecified+no_connect"))
    )
    (net (code "96") (name "unconnected-(U3-SUSPENDb-Pad15)") (class "Default")
      (node (ref "U3") (pin "15") (pinfunction "SUSPENDb_15") (pintype "unspecified+no_connect"))
    )
    (net (code "97") (name "unconnected-(U5-NC-Pad3)") (class "Default")
      (node (ref "U5") (pin "3") (pinfunction "NC_3") (pintype "unspecified+no_connect"))
    )
    (net (code "98") (name "unconnected-(U5-NC-Pad4)") (class "Default")
      (node (ref "U5") (pin "4") (pinfunction "NC_4") (pintype "unspecified+no_connect"))
    )
    (net (code "99") (name "unconnected-(U6-n{slash}a-Pad4)") (class "Default")
      (node (ref "U6") (pin "4") (pinfunction "n/a_4") (pintype "unspecified+no_connect"))
    )
    (net (code "100") (name "unconnected-(U10-PC13-TAMPER-RTC-Pad2)") (class "Default")
      (node (ref "U10") (pin "2") (pinfunction "PC13-TAMPER-RTC_2") (pintype "unspecified+no_connect"))
    )
    (net (code "101") (name "unconnected-(U10-PD0-OSCIN-Pad5)") (class "Default")
      (node (ref "U10") (pin "5") (pinfunction "PD0-OSCIN_5") (pintype "unspecified+no_connect"))
    )
    (net (code "102") (name "unconnected-(U10-PD1-OSCOUT-Pad6)") (class "Default")
      (node (ref "U10") (pin "6") (pinfunction "PD1-OSCOUT_6") (pintype "unspecified+no_connect"))
    )
    (net (code "103") (name "unconnected-(U11-NC-Pad20)") (class "Default")
      (node (ref "U11") (pin "20") (pinfunction "NC_20") (pintype "input+no_connect"))
    )
    (net (code "104") (name "unconnected-(U11-P00-Pad6)") (class "Default")
      (node (ref "U11") (pin "6") (pinfunction "P00_6") (pintype "input+no_connect"))
    )
    (net (code "105") (name "unconnected-(U15-NC-Pad4)") (class "Default")
      (node (ref "U15") (pin "4") (pinfunction "NC_4") (pintype "unspecified+no_connect"))
    )
    (net (code "106") (name "unconnected-(USB1-SBUS1-PadA8)") (class "Default")
      (node (ref "USB1") (pin "A8") (pinfunction "SBUS1_A8") (pintype "input+no_connect"))
    )
    (net (code "107") (name "unconnected-(USB1-SBUS2-PadB8)") (class "Default")
      (node (ref "USB1") (pin "B8") (pinfunction "SBUS2_B8") (pintype "input+no_connect"))
    )
  )
)
